# Top_Level.net
KiCad netlist of a schematic drawn in Altium Designer
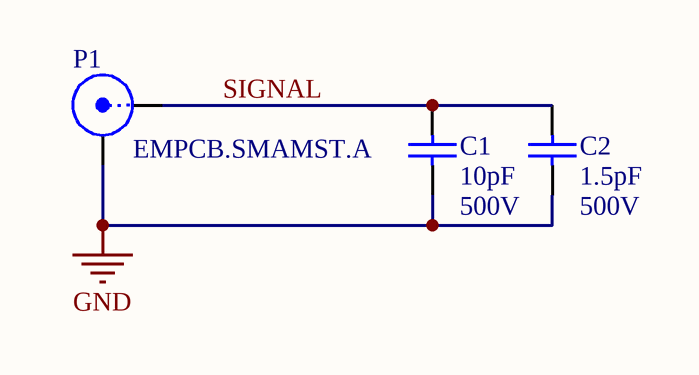
[diagram p0: Top Level.SchDoc]

(export (version "E")
  (design (tool "Eeschema 10.0.6"))
  (components
    (comp (ref "C1")
      (value "10pF")
      (footprint "CAP_1111_ATC 800B")
      (fields (field (name "VOLTAGE") "500V") (field (name "Comment") "800B100JT500XT1K"))
      (libsource (lib "University of Pennsylvania (ESE)") (part "cap"))
    )
    (comp (ref "C2")
      (value "1.5pF")
      (footprint "CAP_1111_ATC 800B")
      (fields (field (name "VOLTAGE") "500V") (field (name "Comment") "800B1R5BT500XT1K"))
      (libsource (lib "University of Pennsylvania (ESE)") (part "cap"))
    )
    (comp (ref "P1")
      (value "EMPCB.SMAMST.A")
      (footprint "FP-EMPCB.SMAMST.A")
      (description "Rf Coax Connector, Sma Plug, 50 Ohm, Edge Mnt; SMA Plug")
      (libsource (lib "University of Pennsylvania (ESE)") (part "RF Plug"))
    )
  )
  (nets
    (net (code "1") (name "/SIGNAL") (class "Default")
      (node (ref "C1") (pin "2") (pinfunction "2_2") (pintype "passive"))
      (node (ref "C2") (pin "2") (pinfunction "2_2") (pintype "passive"))
      (node (ref "P1") (pin "1") (pinfunction "1_1") (pintype "passive"))
    )
    (net (code "2") (name "GND") (class "Default")
      (node (ref "C1") (pin "1") (pinfunction "1_1") (pintype "passive"))
      (node (ref "C2") (pin "1") (pinfunction "1_1") (pintype "passive"))
      (node (ref "P1") (pin "2") (pinfunction "SHELL_2") (pintype "passive"))
    )
  )
)
